# Y_line_07.net
KiCad netlist of a schematic drawn in Altium Designer
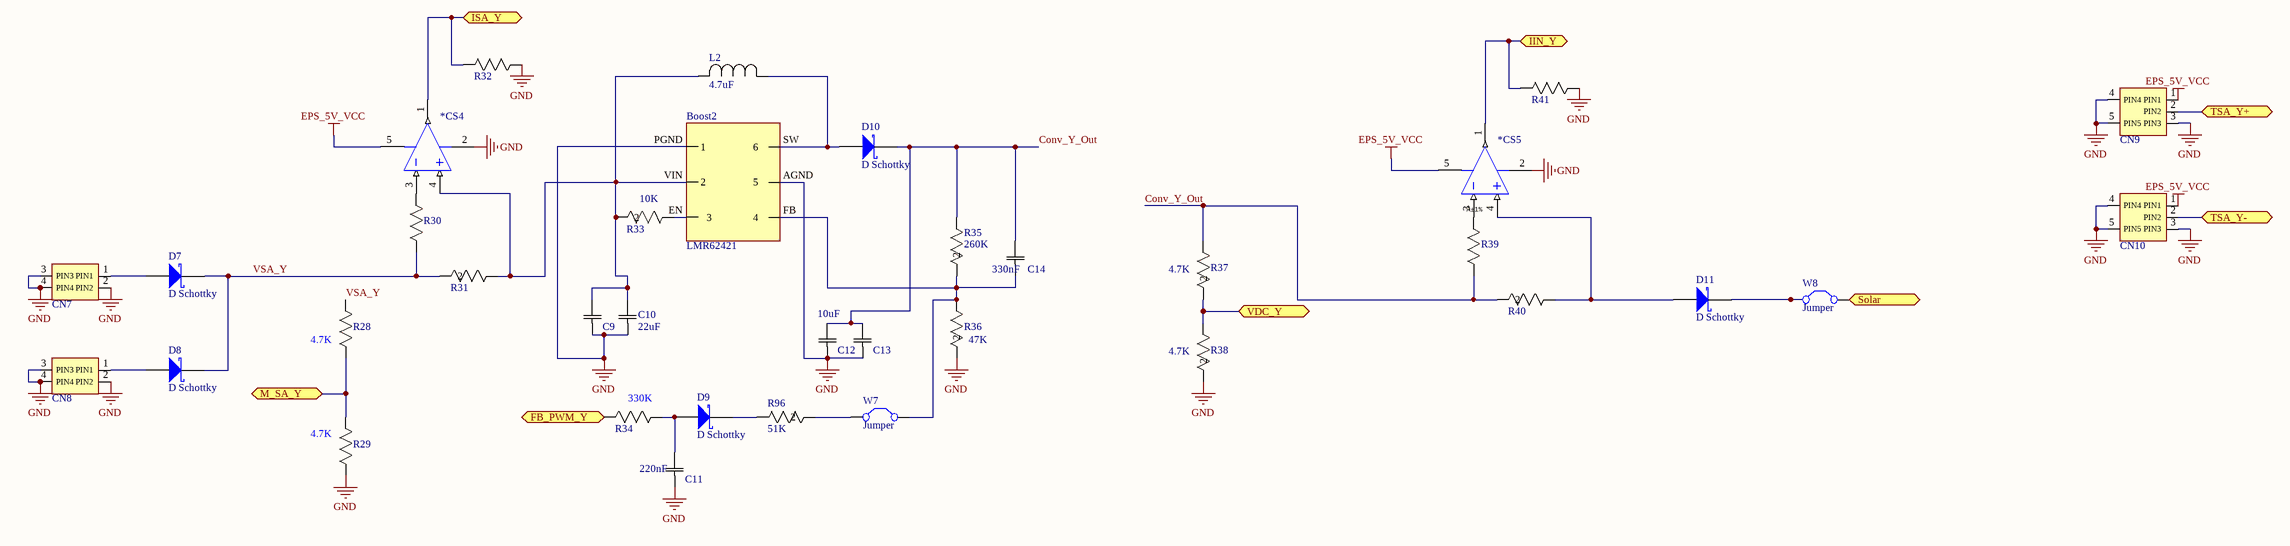
[diagram p0: Y_line_07.SchDoc]

(export (version "E")
  (design (tool "Eeschema 10.0.6"))
  (components
    (comp (ref "*CS4")
      (value "CS4")
      (footprint "LT-S5-5-TSOT-23_N")
      (fields
        (field (name "LINEAR TECHNOLOGY PART NUMBER") "LT6106")
        (field (name "MANUFACTURER") "Linear Technology")
        (field (name "PARTNUMBER") "LT6106HS5#TRMPBF")
      )
      (libsource (lib "Linear Technology Operational Amplifiers (LT2000-LT6000)") (part "LT6106HS5#TRMPBF"))
    )
    (comp (ref "*CS5")
      (value "CS5")
      (footprint "LT-S5-5-TSOT-23_N")
      (fields
        (field (name "LINEAR TECHNOLOGY PART NUMBER") "LT6106")
        (field (name "MANUFACTURER") "Linear Technology")
        (field (name "PARTNUMBER") "LT6106HS5#TRMPBF")
      )
      (libsource (lib "Linear Technology Operational Amplifiers (LT2000-LT6000)") (part "LT6106HS5#TRMPBF"))
    )
    (comp (ref "Boost2")
      (value "LMR62421")
      (footprint "PcbLib_2:LMR62421")
      (description "LMR62421XSDDEMO: 12V @ 500mA, 2.7 ~ 5.5V in")
      (libsource (lib "LMR62421_2") (part "Component_1"))
    )
    (comp (ref "C9")
      (value "GRM155R71H103KA8")
      (footprint "RC0805N")
      (description "Ceramic Capacitor 0402")
      (fields
        (field (name "MANUFACTURER_PART_NUMBER") "GRM155R71H103KA88D")
        (field (name "COPYRIGHT") "Copyright (C) 2015 Accelerated Designs. All rights reserved")
      )
      (libsource (lib "Schlib1") (part "GRM155R71H103KA8"))
    )
    (comp (ref "C10")
      (value "22uF")
      (footprint "RC0805N")
      (description "Ceramic Capacitor")
      (fields
        (field (name "MANUFACTURER_PART_NUMBER") "GRM155R71H103KA88D")
        (field (name "COPYRIGHT") "Copyright (C) 2015 Accelerated Designs. All rights reserved")
      )
      (libsource (lib "PCDU_Library") (part "GRM155R71H103KA8"))
    )
    (comp (ref "C11")
      (value "220nF")
      (footprint "RC0805N")
      (description "Ceramic Capacitor 47uF 0603")
      (fields
        (field (name "MANUFACTURER_PART_NUMBER") "GRM188R71H472KA01D")
        (field (name "COPYRIGHT") "Copyright (C) 2015 Accelerated Designs. All rights reserved")
      )
      (libsource (lib "Schlib1") (part "GRM188R71H472KA0"))
    )
    (comp (ref "C12")
      (value "10uF")
      (footprint "PcbLib1:RC0805N")
      (description "Ceramic Capacitor 47uF 0603")
      (fields
        (field (name "MANUFACTURER_PART_NUMBER") "GRM188R71H472KA01D")
        (field (name "COPYRIGHT") "Copyright (C) 2015 Accelerated Designs. All rights reserved")
      )
      (libsource (lib "PCDU_Library") (part "GRM188R71H472KA0"))
    )
    (comp (ref "C13")
      (value "GRM155R71H103KA8")
      (footprint "RC0805N")
      (description "Ceramic Capacitor 0402")
      (fields
        (field (name "MANUFACTURER_PART_NUMBER") "GRM155R71H103KA88D")
        (field (name "COPYRIGHT") "Copyright (C) 2015 Accelerated Designs. All rights reserved")
      )
      (libsource (lib "Schlib1") (part "GRM155R71H103KA8"))
    )
    (comp (ref "C14")
      (value "330nF")
      (footprint "RC0805N")
      (description "Ceramic Capacitor")
      (fields
        (field (name "MANUFACTURER_PART_NUMBER") "GRM155R71H103KA88D")
        (field (name "COPYRIGHT") "Copyright (C) 2015 Accelerated Designs. All rights reserved")
      )
      (libsource (lib "PCDU_Library") (part "GRM155R71H103KA8"))
    )
    (comp (ref "CN7")
      (value "SM02B-SRSS")
      (footprint "2pins")
      (description "CONN HEADER SH 2POS SIDE 1MM TIN")
      (fields
        (field (name "DIGI-KEY PART NUMBER") "455-1802-1-ND")
        (field (name "MANUFACTURER PART NUMBER") "SM02B-SRSS-TB(LF)(SN)")
      )
      (libsource (lib "EPS_lib") (part "2Pin_Connector"))
    )
    (comp (ref "CN8")
      (value "SM02B-SRSS")
      (footprint "2pins")
      (description "CONN HEADER SH 2POS SIDE 1MM TIN")
      (fields
        (field (name "DIGI-KEY PART NUMBER") "455-1802-1-ND")
        (field (name "MANUFACTURER PART NUMBER") "SM02B-SRSS-TB(LF)(SN)")
      )
      (libsource (lib "EPS_lib") (part "2Pin_Connector"))
    )
    (comp (ref "CN9")
      (value "SM03B-SRSS")
      (footprint "PcbLib1:3pins")
      (description "CONN HEADER SH 3POS SIDE 1MM TIN")
      (fields
        (field (name "DIGI-KEY PART NUMBER") "455-1803-1-ND")
        (field (name "MANUFACTURER PART NUMBER") "SM03B-SRSS-TB(LF)(SN)")
      )
      (libsource (lib "EPS_lib") (part "3PIN_Connector"))
    )
    (comp (ref "CN10")
      (value "SM03B-SRSS")
      (footprint "PcbLib1:3pins")
      (description "CONN HEADER SH 3POS SIDE 1MM TIN")
      (fields
        (field (name "DIGI-KEY PART NUMBER") "455-1803-1-ND")
        (field (name "MANUFACTURER PART NUMBER") "SM03B-SRSS-TB(LF)(SN)")
      )
      (libsource (lib "EPS_lib") (part "3PIN_Connector"))
    )
    (comp (ref "D7")
      (value "D Schottky")
      (footprint "SMB")
      (description "Schottky Diode, 1A")
      (fields (field (name "PUBLISHER") "Altium Limited"))
      (libsource (lib "PCDU_Library") (part "D Schottky"))
    )
    (comp (ref "D8")
      (value "D Schottky")
      (footprint "SMB")
      (description "Schottky Diode, 1A")
      (fields (field (name "PUBLISHER") "Altium Limited"))
      (libsource (lib "PCDU_Library") (part "D Schottky"))
    )
    (comp (ref "D9")
      (value "D Schottky")
      (footprint "SMB")
      (description "Schottky Diode, 1A")
      (fields (field (name "PUBLISHER") "Altium Limited"))
      (libsource (lib "Schlib1") (part "D Schottky"))
    )
    (comp (ref "D10")
      (value "D Schottky")
      (footprint "SMB")
      (description "Schottky Diode, 1A")
      (fields (field (name "PUBLISHER") "Altium Limited"))
      (libsource (lib "PCDU_Library") (part "D Schottky"))
    )
    (comp (ref "D11")
      (value "D Schottky")
      (footprint "SMB")
      (description "Schottky Diode, 1A")
      (fields (field (name "PUBLISHER") "Altium Limited"))
      (libsource (lib "PCDU_Library") (part "D Schottky"))
    )
    (comp (ref "L2")
      (value "4.7uF")
      (footprint "IND_SPM6530")
      (description "Inductor, 4.7uH")
      (fields
        (field (name "MANUFACTURER_PART_NUMBER") "SPM6530T-4R7M")
        (field (name "COPYRIGHT") "Copyright (C) 2015 Accelerated Designs. All rights reserved")
      )
      (libsource (lib "PCDU_Library") (part "SPM6530T-4R7M"))
    )
    (comp (ref "R28")
      (value "RC0805FR")
      (footprint "RC0805N")
      (description "Thick Film Resistors 0805")
      (fields
        (field (name "DIGIKEYPARTNUMBER") "311-4.70KCRTR-ND")
        (field (name "MANUFACTURER_PART_NUMBER") "RC0805FR-074K7L")
        (field (name "RESISTANCE_(OHMS)") "4.7K")
        (field (name "COPYRIGHT") "Copyright (C) 2015 Accelerated Designs. All rights reserved")
      )
      (libsource (lib "Schlib1") (part "RC0805FR"))
    )
    (comp (ref "R29")
      (value "RC0805FR")
      (footprint "RC0805N")
      (description "Thick Film Resistors 0805")
      (fields
        (field (name "DIGIKEYPARTNUMBER") "311-4.70KCRTR-ND")
        (field (name "MANUFACTURER_PART_NUMBER") "RC0805FR-074K7L")
        (field (name "RESISTANCE_(OHMS)") "4.7K")
        (field (name "COPYRIGHT") "Copyright (C) 2015 Accelerated Designs. All rights reserved")
      )
      (libsource (lib "Schlib1") (part "RC0805FR"))
    )
    (comp (ref "R30")
      (value "RC0805FR")
      (footprint "RC0805N")
      (description "Thick Film Resistors 0805")
      (fields
        (field (name "DIGIKEYPARTNUMBER") "311-4.70KCRTR-ND")
        (field (name "MANUFACTURER_PART_NUMBER") "RC0805FR-074K7L")
        (field (name "COPYRIGHT") "Copyright (C) 2015 Accelerated Designs. All rights reserved")
      )
      (libsource (lib "Schlib1") (part "RC0805FR"))
    )
    (comp (ref "R31")
      (value "RL0805FR-070R1L")
      (footprint "RC0805N")
      (description "Sense Resistor 100m ohm 0805")
      (fields
        (field (name "DIGIKEYPARTNUMBER") "311-.10STR-ND")
        (field (name "TOLERANCE") "Â±1%")
        (field (name "COPYRIGHT") "Copyright (C) 2015 Accelerated Designs. All rights reserved")
      )
      (libsource (lib "Schlib1") (part "RL0805FR-070R1L"))
    )
    (comp (ref "R32")
      (value "RC0805FR")
      (footprint "RC0805N")
      (description "Thick Film Resistors 0805")
      (fields
        (field (name "DIGIKEYPARTNUMBER") "311-4.70KCRTR-ND")
        (field (name "MANUFACTURER_PART_NUMBER") "RC0805FR-074K7L")
        (field (name "COPYRIGHT") "Copyright (C) 2015 Accelerated Designs. All rights reserved")
      )
      (libsource (lib "Schlib1") (part "RC0805FR"))
    )
    (comp (ref "R33")
      (value "10K")
      (footprint "RC0805N")
      (description "Thick Film Resistors 0805")
      (fields
        (field (name "DIGIKEYPARTNUMBER") "311-4.70KCRTR-ND")
        (field (name "MANUFACTURER_PART_NUMBER") "RC0805FR-074K7L")
        (field (name "COPYRIGHT") "Copyright (C) 2015 Accelerated Designs. All rights reserved")
      )
      (libsource (lib "PCDU_Library") (part "RC0805FR"))
    )
    (comp (ref "R34")
      (value "RC0805FR")
      (footprint "RC0805N")
      (description "Thick Film Resistors 0805")
      (fields
        (field (name "DIGIKEYPARTNUMBER") "311-4.70KCRTR-ND")
        (field (name "MANUFACTURER_PART_NUMBER") "RC0805FR-074K7L")
        (field (name "RESISTANCE_(OHMS)") "330K")
        (field (name "COPYRIGHT") "Copyright (C) 2015 Accelerated Designs. All rights reserved")
      )
      (libsource (lib "Schlib1") (part "RC0805FR"))
    )
    (comp (ref "R35")
      (value "260K")
      (footprint "RC0805N")
      (description "Thick Film Resistors 0805")
      (fields
        (field (name "DIGIKEYPARTNUMBER") "311-4.70KCRTR-ND")
        (field (name "MANUFACTURER_PART_NUMBER") "RC0805FR-074K7L")
        (field (name "COPYRIGHT") "Copyright (C) 2015 Accelerated Designs. All rights reserved")
      )
      (libsource (lib "PCDU_Library") (part "RC0805FR"))
    )
    (comp (ref "R36")
      (value "47K")
      (footprint "RC0805N")
      (description "Thick Film Resistors 0805")
      (fields
        (field (name "DIGIKEYPARTNUMBER") "311-4.70KCRTR-ND")
        (field (name "MANUFACTURER_PART_NUMBER") "RC0805FR-074K7L")
        (field (name "COPYRIGHT") "Copyright (C) 2015 Accelerated Designs. All rights reserved")
      )
      (libsource (lib "PCDU_Library") (part "RC0805FR"))
    )
    (comp (ref "R37")
      (value "4.7K")
      (footprint "RC0805N")
      (description "Thick Film Resistors 0805")
      (fields
        (field (name "DIGIKEYPARTNUMBER") "311-4.70KCRTR-ND")
        (field (name "MANUFACTURER_PART_NUMBER") "RC0805FR-074K7L")
        (field (name "COPYRIGHT") "Copyright (C) 2015 Accelerated Designs. All rights reserved")
      )
      (libsource (lib "PCDU_Library") (part "RC0805FR"))
    )
    (comp (ref "R38")
      (value "4.7K")
      (footprint "RC0805N")
      (description "Thick Film Resistors 0805")
      (fields
        (field (name "DIGIKEYPARTNUMBER") "311-4.70KCRTR-ND")
        (field (name "MANUFACTURER_PART_NUMBER") "RC0805FR-074K7L")
        (field (name "COPYRIGHT") "Copyright (C) 2015 Accelerated Designs. All rights reserved")
      )
      (libsource (lib "PCDU_Library") (part "RC0805FR"))
    )
    (comp (ref "R39")
      (value "RC0805FR")
      (footprint "RC0805N")
      (description "Thick Film Resistors 0805")
      (fields
        (field (name "DIGIKEYPARTNUMBER") "311-4.70KCRTR-ND")
        (field (name "MANUFACTURER_PART_NUMBER") "RC0805FR-074K7L")
        (field (name "TOLERANCE") "Â±1%")
        (field (name "COPYRIGHT") "Copyright (C) 2015 Accelerated Designs. All rights reserved")
      )
      (libsource (lib "Schlib1") (part "RC0805FR"))
    )
    (comp (ref "R40")
      (value "RL0805FR-070R1L")
      (footprint "RC0805N")
      (description "Sense Resistor 100m ohm 0805")
      (fields
        (field (name "DIGIKEYPARTNUMBER") "311-.10STR-ND")
        (field (name "TOLERANCE") "Â±1%")
        (field (name "COPYRIGHT") "Copyright (C) 2015 Accelerated Designs. All rights reserved")
      )
      (libsource (lib "Schlib1") (part "RL0805FR-070R1L"))
    )
    (comp (ref "R41")
      (value "RC0805FR")
      (footprint "RC0805N")
      (description "Thick Film Resistors 0805")
      (fields
        (field (name "DIGIKEYPARTNUMBER") "311-4.70KCRTR-ND")
        (field (name "MANUFACTURER_PART_NUMBER") "RC0805FR-074K7L")
        (field (name "COPYRIGHT") "Copyright (C) 2015 Accelerated Designs. All rights reserved")
      )
      (libsource (lib "Schlib1") (part "RC0805FR"))
    )
    (comp (ref "R96")
      (value "51K")
      (footprint "RC0805N")
      (description "Thick Film Resistors 0805")
      (fields
        (field (name "DIGIKEYPARTNUMBER") "311-4.70KCRTR-ND")
        (field (name "MANUFACTURER_PART_NUMBER") "RC0805FR-074K7L")
        (field (name "COPYRIGHT") "Copyright (C) 2015 Accelerated Designs. All rights reserved")
      )
      (libsource (lib "PCDU_Library") (part "RC0805FR"))
    )
    (comp (ref "W7")
      (value "Jumper")
      (footprint "PcbLib1:RAD-0.1")
      (description "Jumper Wire")
      (fields (field (name "PUBLISHER") "Altium Limited"))
      (libsource (lib "PCDU_Library") (part "Jumper"))
    )
    (comp (ref "W8")
      (value "Jumper")
      (footprint "PcbLib1:RAD-0.1")
      (description "Jumper Wire")
      (fields (field (name "PUBLISHER") "Altium Limited"))
      (libsource (lib "PCDU_Library") (part "Jumper"))
    )
  )
  (nets
    (net (code "1") (name "/Conv_Y_Out") (class "Default")
      (node (ref "C12") (pin "2") (pinfunction "2_2") (pintype "passive"))
      (node (ref "C13") (pin "2") (pinfunction "2_2") (pintype "passive"))
      (node (ref "C14") (pin "2") (pinfunction "2_2") (pintype "passive"))
      (node (ref "D10") (pin "2") (pinfunction "K_2") (pintype "passive"))
      (node (ref "R35") (pin "1") (pinfunction "1_1") (pintype "passive"))
      (node (ref "R37") (pin "1") (pinfunction "1_1") (pintype "passive"))
      (node (ref "R39") (pin "2") (pinfunction "2_2") (pintype "passive"))
      (node (ref "R40") (pin "2") (pinfunction "2_2") (pintype "passive"))
    )
    (net (code "2") (name "/FB_PWM_Y") (class "Default")
      (node (ref "R34") (pin "2") (pinfunction "2_2") (pintype "passive"))
    )
    (net (code "3") (name "/IIN_Y") (class "Default")
      (node (ref "*CS5") (pin "1") (pinfunction "OUT_1") (pintype "output"))
      (node (ref "R41") (pin "1") (pinfunction "1_1") (pintype "passive"))
    )
    (net (code "4") (name "/ISA_Y") (class "Default")
      (node (ref "*CS4") (pin "1") (pinfunction "OUT_1") (pintype "output"))
      (node (ref "R32") (pin "1") (pinfunction "1_1") (pintype "passive"))
    )
    (net (code "5") (name "/M_SA_Y") (class "Default")
      (node (ref "R28") (pin "2") (pinfunction "2_2") (pintype "passive"))
      (node (ref "R29") (pin "1") (pinfunction "1_1") (pintype "passive"))
    )
    (net (code "6") (name "/Solar") (class "Default")
      (node (ref "W8") (pin "2") (pinfunction "C2_2") (pintype "passive"))
    )
    (net (code "7") (name "/TSA_Y+") (class "Default")
      (node (ref "CN9") (pin "2") (pinfunction "PIN2_2") (pintype "passive"))
    )
    (net (code "8") (name "/TSA_Y-") (class "Default")
      (node (ref "CN10") (pin "2") (pinfunction "PIN2_2") (pintype "passive"))
    )
    (net (code "9") (name "/VDC_Y") (class "Default")
      (node (ref "R37") (pin "2") (pinfunction "2_2") (pintype "passive"))
      (node (ref "R38") (pin "1") (pinfunction "1_1") (pintype "passive"))
    )
    (net (code "10") (name "/VSA_Y") (class "Default")
      (node (ref "D7") (pin "2") (pinfunction "K_2") (pintype "passive"))
      (node (ref "D8") (pin "2") (pinfunction "K_2") (pintype "passive"))
      (node (ref "R28") (pin "1") (pinfunction "1_1") (pintype "passive"))
      (node (ref "R30") (pin "2") (pinfunction "2_2") (pintype "passive"))
      (node (ref "R31") (pin "2") (pinfunction "2_2") (pintype "passive"))
    )
    (net (code "11") (name "EPS_5V_VCC") (class "Default")
      (node (ref "*CS4") (pin "5") (pinfunction "V+_5") (pintype "power_in"))
      (node (ref "*CS5") (pin "5") (pinfunction "V+_5") (pintype "power_in"))
      (node (ref "CN10") (pin "1") (pinfunction "PIN1_1") (pintype "passive"))
      (node (ref "CN9") (pin "1") (pinfunction "PIN1_1") (pintype "passive"))
    )
    (net (code "12") (name "GND") (class "Default")
      (node (ref "*CS4") (pin "2") (pinfunction "V-_2") (pintype "power_in"))
      (node (ref "*CS5") (pin "2") (pinfunction "V-_2") (pintype "power_in"))
      (node (ref "Boost2") (pin "AGND") (pinfunction "5_AGND") (pintype "passive"))
      (node (ref "Boost2") (pin "PGND") (pinfunction "1_PGND") (pintype "passive"))
      (node (ref "C10") (pin "1") (pinfunction "1_1") (pintype "passive"))
      (node (ref "C11") (pin "1") (pinfunction "1_1") (pintype "passive"))
      (node (ref "C12") (pin "1") (pinfunction "1_1") (pintype "passive"))
      (node (ref "C13") (pin "1") (pinfunction "1_1") (pintype "passive"))
      (node (ref "C9") (pin "1") (pinfunction "1_1") (pintype "passive"))
      (node (ref "CN10") (pin "3") (pinfunction "PIN3_3") (pintype "passive"))
      (node (ref "CN10") (pin "4") (pinfunction "PIN4_4") (pintype "passive"))
      (node (ref "CN10") (pin "5") (pinfunction "PIN5_5") (pintype "passive"))
      (node (ref "CN7") (pin "2") (pinfunction "PIN2_2") (pintype "passive"))
      (node (ref "CN7") (pin "3") (pinfunction "PIN3_3") (pintype "passive"))
      (node (ref "CN7") (pin "4") (pinfunction "PIN4_4") (pintype "passive"))
      (node (ref "CN8") (pin "2") (pinfunction "PIN2_2") (pintype "passive"))
      (node (ref "CN8") (pin "3") (pinfunction "PIN3_3") (pintype "passive"))
      (node (ref "CN8") (pin "4") (pinfunction "PIN4_4") (pintype "passive"))
      (node (ref "CN9") (pin "3") (pinfunction "PIN3_3") (pintype "passive"))
      (node (ref "CN9") (pin "4") (pinfunction "PIN4_4") (pintype "passive"))
      (node (ref "CN9") (pin "5") (pinfunction "PIN5_5") (pintype "passive"))
      (node (ref "R29") (pin "2") (pinfunction "2_2") (pintype "passive"))
      (node (ref "R32") (pin "2") (pinfunction "2_2") (pintype "passive"))
      (node (ref "R36") (pin "2") (pinfunction "2_2") (pintype "passive"))
      (node (ref "R38") (pin "2") (pinfunction "2_2") (pintype "passive"))
      (node (ref "R41") (pin "2") (pinfunction "2_2") (pintype "passive"))
    )
    (net (code "13") (name "Net-(*CS4-+IN)") (class "Default")
      (node (ref "*CS4") (pin "4") (pinfunction "+IN_4") (pintype "input"))
      (node (ref "Boost2") (pin "VIN") (pinfunction "2_VIN") (pintype "passive"))
      (node (ref "C10") (pin "2") (pinfunction "2_2") (pintype "passive"))
      (node (ref "C9") (pin "2") (pinfunction "2_2") (pintype "passive"))
      (node (ref "L2") (pin "2") (pinfunction "2_2") (pintype "passive"))
      (node (ref "R31") (pin "1") (pinfunction "1_1") (pintype "passive"))
      (node (ref "R33") (pin "2") (pinfunction "2_2") (pintype "passive"))
    )
    (net (code "14") (name "Net-(*CS4--IN)") (class "Default")
      (node (ref "*CS4") (pin "3") (pinfunction "-IN_3") (pintype "input"))
      (node (ref "R30") (pin "1") (pinfunction "1_1") (pintype "passive"))
    )
    (net (code "15") (name "Net-(*CS5-+IN)") (class "Default")
      (node (ref "*CS5") (pin "4") (pinfunction "+IN_4") (pintype "input"))
      (node (ref "D11") (pin "1") (pinfunction "A_1") (pintype "passive"))
      (node (ref "R40") (pin "1") (pinfunction "1_1") (pintype "passive"))
    )
    (net (code "16") (name "Net-(*CS5--IN)") (class "Default")
      (node (ref "*CS5") (pin "3") (pinfunction "-IN_3") (pintype "input"))
      (node (ref "R39") (pin "1") (pinfunction "1_1") (pintype "passive"))
    )
    (net (code "17") (name "Net-(Boost2-3)") (class "Default")
      (node (ref "Boost2") (pin "EN") (pinfunction "3_EN") (pintype "passive"))
      (node (ref "R33") (pin "1") (pinfunction "1_1") (pintype "passive"))
    )
    (net (code "18") (name "Net-(Boost2-4)") (class "Default")
      (node (ref "Boost2") (pin "FB") (pinfunction "4_FB") (pintype "passive"))
      (node (ref "C14") (pin "1") (pinfunction "1_1") (pintype "passive"))
      (node (ref "R35") (pin "2") (pinfunction "2_2") (pintype "passive"))
      (node (ref "R36") (pin "1") (pinfunction "1_1") (pintype "passive"))
      (node (ref "W7") (pin "2") (pinfunction "C2_2") (pintype "passive"))
    )
    (net (code "19") (name "Net-(Boost2-6)") (class "Default")
      (node (ref "Boost2") (pin "SW") (pinfunction "6_SW") (pintype "passive"))
      (node (ref "D10") (pin "1") (pinfunction "A_1") (pintype "passive"))
      (node (ref "L2") (pin "1") (pinfunction "1_1") (pintype "passive"))
    )
    (net (code "20") (name "Net-(CN7-PIN1)") (class "Default")
      (node (ref "CN7") (pin "1") (pinfunction "PIN1_1") (pintype "passive"))
      (node (ref "D7") (pin "1") (pinfunction "A_1") (pintype "passive"))
    )
    (net (code "21") (name "Net-(CN8-PIN1)") (class "Default")
      (node (ref "CN8") (pin "1") (pinfunction "PIN1_1") (pintype "passive"))
      (node (ref "D8") (pin "1") (pinfunction "A_1") (pintype "passive"))
    )
    (net (code "22") (name "Net-(D9-A)") (class "Default")
      (node (ref "C11") (pin "2") (pinfunction "2_2") (pintype "passive"))
      (node (ref "D9") (pin "1") (pinfunction "A_1") (pintype "passive"))
      (node (ref "R34") (pin "1") (pinfunction "1_1") (pintype "passive"))
    )
    (net (code "23") (name "Net-(D9-K)") (class "Default")
      (node (ref "D9") (pin "2") (pinfunction "K_2") (pintype "passive"))
      (node (ref "R96") (pin "1") (pinfunction "1_1") (pintype "passive"))
    )
    (net (code "24") (name "Net-(D11-K)") (class "Default")
      (node (ref "D11") (pin "2") (pinfunction "K_2") (pintype "passive"))
      (node (ref "W8") (pin "1") (pinfunction "C1_1") (pintype "passive"))
    )
    (net (code "25") (name "Net-(W7-C1)") (class "Default")
      (node (ref "R96") (pin "2") (pinfunction "2_2") (pintype "passive"))
      (node (ref "W7") (pin "1") (pinfunction "C1_1") (pintype "passive"))
    )
  )
)
